# power_main_connector.net
KiCad netlist of a schematic drawn in Altium Designer
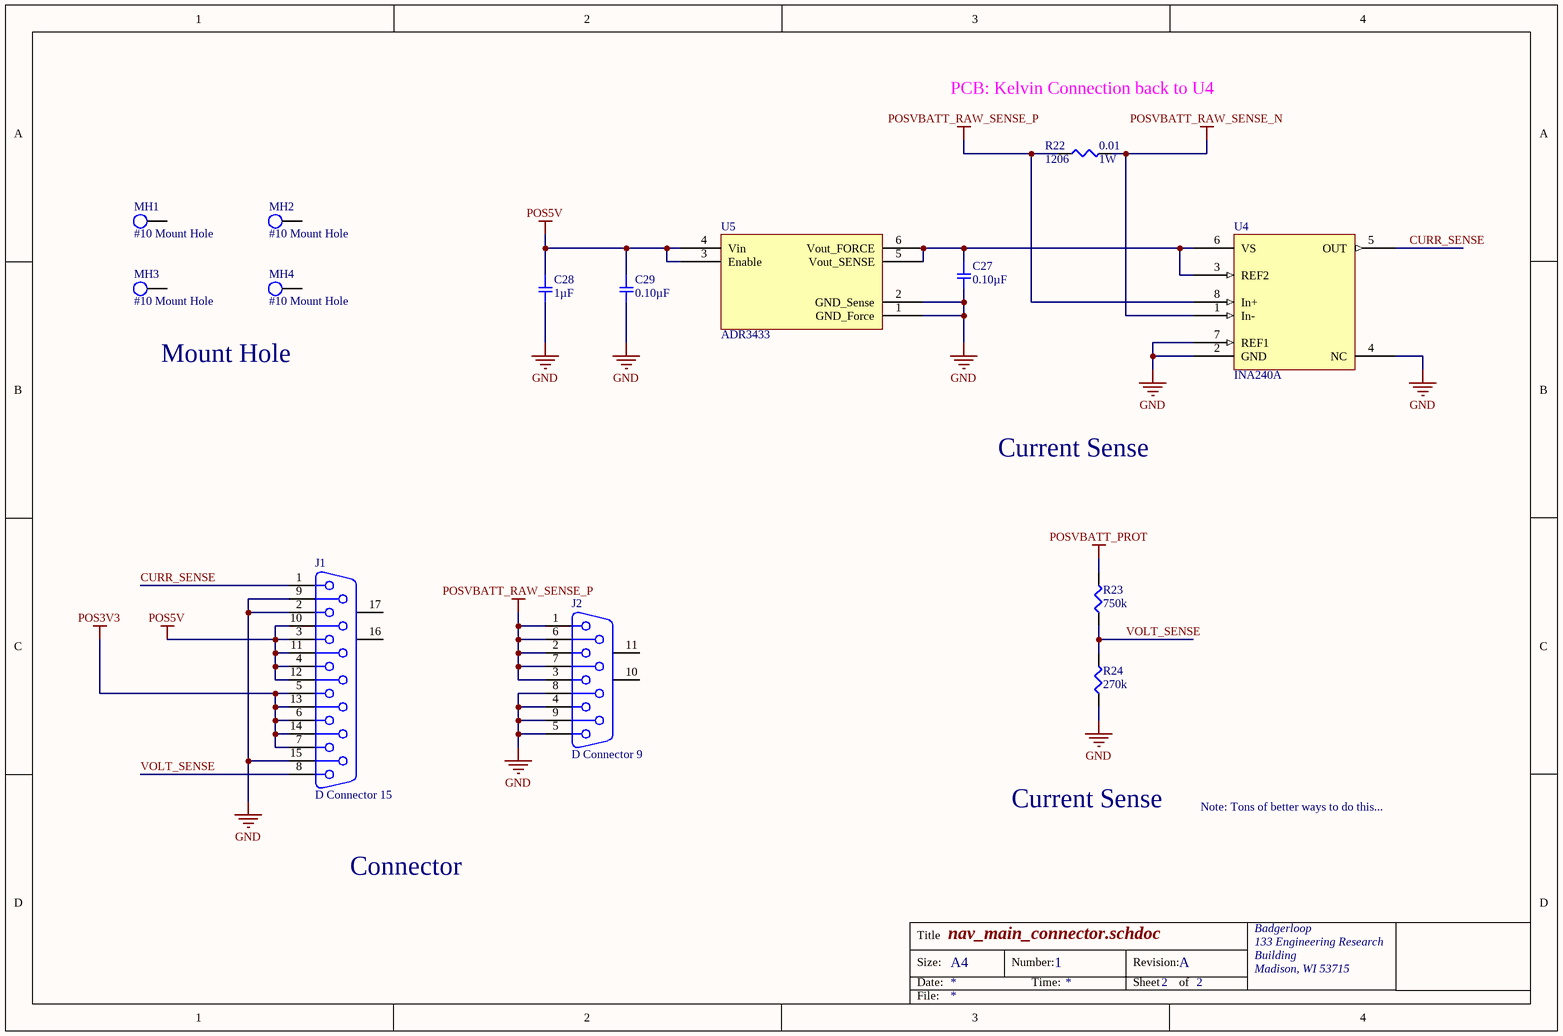
[diagram p0: power_main_connector.SchDoc]

(export (version "E")
  (design (tool "Eeschema 10.0.6"))
  (components
    (comp (ref "C27")
      (value "0.10µF")
      (footprint "SMD-0805C")
      (description "CAP CER 0.1UF 50V X7R 0805")
      (fields
        (field (name "DIGI-KEY PART NUMBER") "490-11955-1-ND")
        (field (name "PART NUMBER") "GCD21BR71H104KA01L")
      )
      (libsource (lib "capacitor") (part "GCD21BR71H104KA01L"))
    )
    (comp (ref "C28")
      (value "1µF")
      (footprint "SMD-0805C")
      (description "CAP CER 1UF 50V X7R 0805")
      (fields
        (field (name "DIGI-KEY PART NUMBER") "490-10667-1-ND")
        (field (name "PART NUMBER") "GCJ21BR71H105KA01L")
      )
      (libsource (lib "capacitor") (part "GCJ21BR71H105KA01L"))
    )
    (comp (ref "C29")
      (value "0.10µF")
      (footprint "SMD-0805C")
      (description "CAP CER 0.1UF 50V X7R 0805")
      (fields
        (field (name "DIGI-KEY PART NUMBER") "490-11955-1-ND")
        (field (name "PART NUMBER") "GCD21BR71H104KA01L")
      )
      (libsource (lib "capacitor") (part "GCD21BR71H104KA01L"))
    )
    (comp (ref "J1")
      (value "D Connector 15")
      (footprint "DSUB1.385-2H15")
      (description "Receptacle Assembly, 15 Position, Right Angle")
      (fields (field (name "PUBLISHER") "Altium Limited"))
      (libsource (lib "connector") (part "D Connector 15"))
    )
    (comp (ref "J2")
      (value "D Connector 9")
      (footprint "DSUB1.385-2H9")
      (description "Receptacle Assembly, 9 Position, Right Angle")
      (fields (field (name "PUBLISHER") "Altium Limited"))
      (libsource (lib "connector") (part "D Connector 9"))
    )
    (comp (ref "MH1")
      (value "#10 Mount Hole")
      (footprint "MH")
      (libsource (lib "misc") (part "#10 Mount Hole"))
    )
    (comp (ref "MH2")
      (value "#10 Mount Hole")
      (footprint "MH")
      (libsource (lib "misc") (part "#10 Mount Hole"))
    )
    (comp (ref "MH3")
      (value "#10 Mount Hole")
      (footprint "MH")
      (libsource (lib "misc") (part "#10 Mount Hole"))
    )
    (comp (ref "MH4")
      (value "#10 Mount Hole")
      (footprint "MH")
      (libsource (lib "misc") (part "#10 Mount Hole"))
    )
    (comp (ref "R22")
      (value "0.01")
      (footprint "SMD-1206-RES")
      (description "RES SMD 0.01 OHM 1% 1W 1206")
      (fields
        (field (name "PART NUMBER") "ERJ-8CWFR010V")
        (field (name "DIGI-KEY PART NUMBER") "P0.01BVCT-ND")
        (field (name "POWER (WATTS)") "1W")
        (field (name "SUPPLIER DEVICE PACKAGE") "1206")
      )
      (libsource (lib "resistor") (part "ERJ-8CWFR010V"))
    )
    (comp (ref "R23")
      (value "750k")
      (footprint "SMD-0805-RES")
      (description "RES SMD 750K OHM 5% 1/8W 0805")
      (fields
        (field (name "PART NUMBER") "ERJ-6GEYJ754V")
        (field (name "DIGI-KEY PART NUMBER") "P750KACT-ND")
      )
      (libsource (lib "resistor") (part "ERJ-6GEYJ754V"))
    )
    (comp (ref "R24")
      (value "270k")
      (footprint "SMD-0805-RES")
      (description "RES SMD 270K OHM 5% 1/8W 0805")
      (fields
        (field (name "PART NUMBER") "ERJ-6GEYJ274V")
        (field (name "DIGI-KEY PART NUMBER") "P270KACT-ND")
      )
      (libsource (lib "resistor") (part "ERJ-6GEYJ274V"))
    )
    (comp (ref "U4")
      (value "INA240A")
      (footprint "SOIC127P600X175-8N")
      (description "IC AMP CURRENT SENSE 8-TSSOP")
      (fields (field (name "MANUFACTURER") "TI"))
      (libsource (lib "ic") (part "INA240A"))
    )
    (comp (ref "U5")
      (value "ADR3433")
      (footprint "SOT95P280X145-6N")
      (description "IC VREF SERIES 3.3V SOT23-6")
      (fields (field (name "MANUFACTURER") "Analog Devices"))
      (libsource (lib "ic") (part "ADR3433"))
    )
  )
  (nets
    (net (code "1") (name "/CURR_SENSE") (class "Default")
      (node (ref "J1") (pin "1") (pinfunction "1_1") (pintype "passive"))
      (node (ref "U4") (pin "5") (pinfunction "OUT_5") (pintype "output"))
    )
    (net (code "2") (name "/VOLT_SENSE") (class "Default")
      (node (ref "J1") (pin "8") (pinfunction "8_8") (pintype "passive"))
      (node (ref "R23") (pin "1") (pinfunction "1_1") (pintype "passive"))
      (node (ref "R24") (pin "2") (pinfunction "2_2") (pintype "passive"))
    )
    (net (code "3") (name "GND") (class "Default")
      (node (ref "C27") (pin "2") (pinfunction "2_2") (pintype "passive"))
      (node (ref "C28") (pin "2") (pinfunction "2_2") (pintype "passive"))
      (node (ref "C29") (pin "2") (pinfunction "2_2") (pintype "passive"))
      (node (ref "J1") (pin "15") (pinfunction "15_15") (pintype "passive"))
      (node (ref "J1") (pin "2") (pinfunction "2_2") (pintype "passive"))
      (node (ref "J1") (pin "9") (pinfunction "9_9") (pintype "passive"))
      (node (ref "J2") (pin "4") (pinfunction "4_4") (pintype "passive"))
      (node (ref "J2") (pin "5") (pinfunction "5_5") (pintype "passive"))
      (node (ref "J2") (pin "8") (pinfunction "8_8") (pintype "passive"))
      (node (ref "J2") (pin "9") (pinfunction "9_9") (pintype "passive"))
      (node (ref "R24") (pin "1") (pinfunction "1_1") (pintype "passive"))
      (node (ref "U4") (pin "2") (pinfunction "GND_2") (pintype "power_in"))
      (node (ref "U4") (pin "4") (pinfunction "NC_4") (pintype "passive"))
      (node (ref "U4") (pin "7") (pinfunction "REF1_7") (pintype "input"))
      (node (ref "U5") (pin "1") (pinfunction "GND_Force_1") (pintype "power_in"))
      (node (ref "U5") (pin "2") (pinfunction "GND_Sense_2") (pintype "power_in"))
    )
    (net (code "4") (name "Net-(U4-REF2)") (class "Default")
      (node (ref "C27") (pin "1") (pinfunction "1_1") (pintype "passive"))
      (node (ref "U4") (pin "3") (pinfunction "REF2_3") (pintype "input"))
      (node (ref "U4") (pin "6") (pinfunction "VS_6") (pintype "power_in"))
      (node (ref "U5") (pin "5") (pinfunction "Vout_SENSE_5") (pintype "passive"))
      (node (ref "U5") (pin "6") (pinfunction "Vout_FORCE_6") (pintype "passive"))
    )
    (net (code "5") (name "POS3V3") (class "Default")
      (node (ref "J1") (pin "13") (pinfunction "13_13") (pintype "passive"))
      (node (ref "J1") (pin "14") (pinfunction "14_14") (pintype "passive"))
      (node (ref "J1") (pin "5") (pinfunction "5_5") (pintype "passive"))
      (node (ref "J1") (pin "6") (pinfunction "6_6") (pintype "passive"))
      (node (ref "J1") (pin "7") (pinfunction "7_7") (pintype "passive"))
    )
    (net (code "6") (name "POS5V") (class "Default")
      (node (ref "C28") (pin "1") (pinfunction "1_1") (pintype "passive"))
      (node (ref "C29") (pin "1") (pinfunction "1_1") (pintype "passive"))
      (node (ref "J1") (pin "10") (pinfunction "10_10") (pintype "passive"))
      (node (ref "J1") (pin "11") (pinfunction "11_11") (pintype "passive"))
      (node (ref "J1") (pin "12") (pinfunction "12_12") (pintype "passive"))
      (node (ref "J1") (pin "3") (pinfunction "3_3") (pintype "passive"))
      (node (ref "J1") (pin "4") (pinfunction "4_4") (pintype "passive"))
      (node (ref "U5") (pin "3") (pinfunction "Enable_3") (pintype "passive"))
      (node (ref "U5") (pin "4") (pinfunction "Vin_4") (pintype "passive"))
    )
    (net (code "7") (name "POSVBATT_PROT") (class "Default")
      (node (ref "R23") (pin "2") (pinfunction "2_2") (pintype "passive"))
    )
    (net (code "8") (name "POSVBATT_RAW_SENSE_N") (class "Default")
      (node (ref "R22") (pin "2") (pinfunction "2_2") (pintype "passive"))
      (node (ref "U4") (pin "1") (pinfunction "In-_1") (pintype "input"))
    )
    (net (code "9") (name "POSVBATT_RAW_SENSE_P") (class "Default")
      (node (ref "J2") (pin "1") (pinfunction "1_1") (pintype "passive"))
      (node (ref "J2") (pin "2") (pinfunction "2_2") (pintype "passive"))
      (node (ref "J2") (pin "3") (pinfunction "3_3") (pintype "passive"))
      (node (ref "J2") (pin "6") (pinfunction "6_6") (pintype "passive"))
      (node (ref "J2") (pin "7") (pinfunction "7_7") (pintype "passive"))
      (node (ref "R22") (pin "1") (pinfunction "1_1") (pintype "passive"))
      (node (ref "U4") (pin "8") (pinfunction "In+_8") (pintype "input"))
    )
    (net (code "10") (name "unconnected-(J1-MH1-Pad16)") (class "Default")
      (node (ref "J1") (pin "16") (pinfunction "MH1_16") (pintype "passive"))
    )
    (net (code "11") (name "unconnected-(J1-MH2-Pad17)") (class "Default")
      (node (ref "J1") (pin "17") (pinfunction "MH2_17") (pintype "passive"))
    )
    (net (code "12") (name "unconnected-(J2-MH1-Pad10)") (class "Default")
      (node (ref "J2") (pin "10") (pinfunction "MH1_10") (pintype "passive"))
    )
    (net (code "13") (name "unconnected-(J2-MH2-Pad11)") (class "Default")
      (node (ref "J2") (pin "11") (pinfunction "MH2_11") (pintype "passive"))
    )
    (net (code "14") (name "unconnected-(MH1-Pad46)") (class "Default")
      (node (ref "MH1") (pin "46") (pinfunction "46_46") (pintype "passive"))
    )
    (net (code "15") (name "unconnected-(MH2-Pad46)") (class "Default")
      (node (ref "MH2") (pin "46") (pinfunction "46_46") (pintype "passive"))
    )
    (net (code "16") (name "unconnected-(MH3-Pad46)") (class "Default")
      (node (ref "MH3") (pin "46") (pinfunction "46_46") (pintype "passive"))
    )
    (net (code "17") (name "unconnected-(MH4-Pad46)") (class "Default")
      (node (ref "MH4") (pin "46") (pinfunction "46_46") (pintype "passive"))
    )
  )
)
